# pomodoro_timer.net
KiCad netlist of a schematic drawn in EAGLE
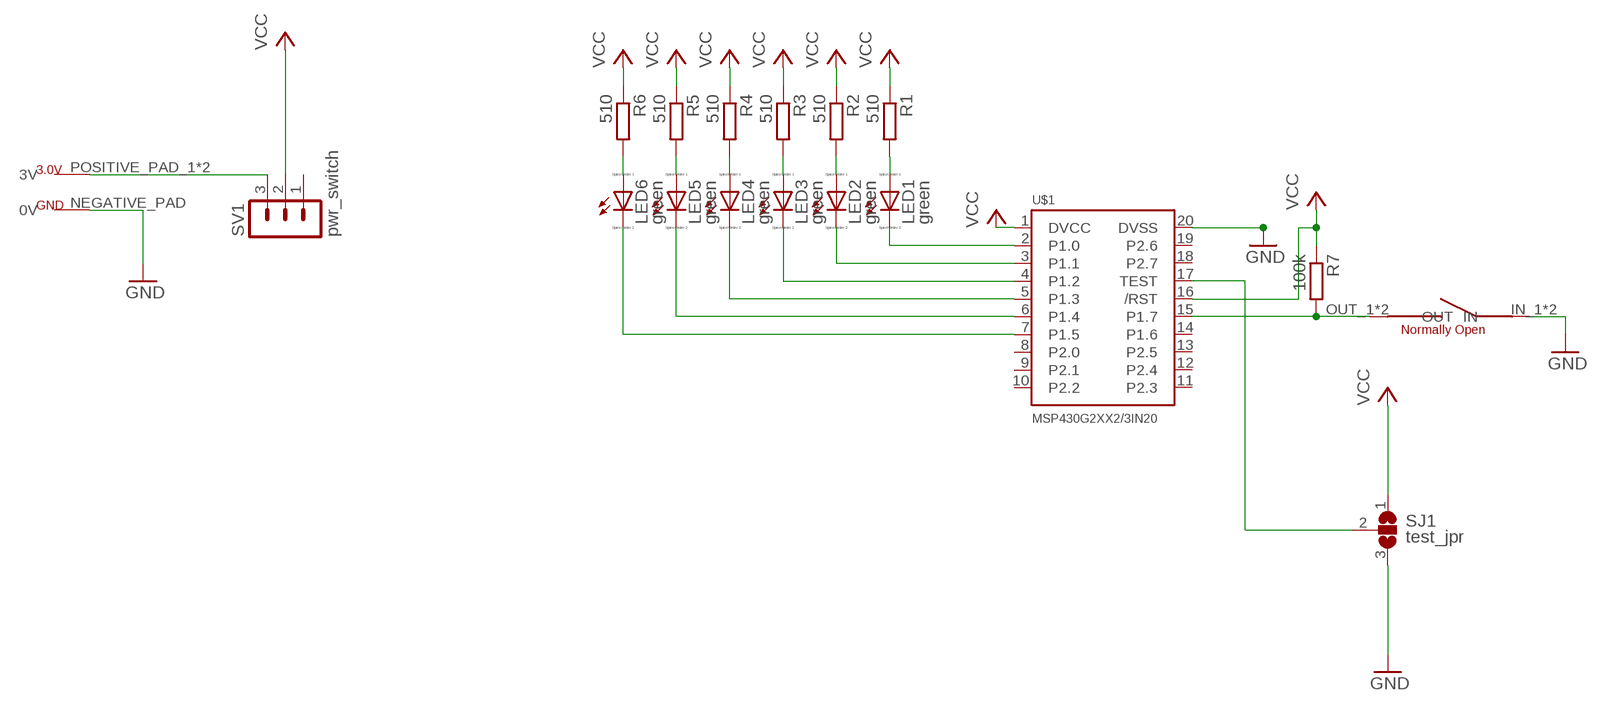
[diagram p0: schematic, sheet 1]

(export (version "E")
  (design (tool "Eeschema 10.0.6"))
  (components
    (comp (ref "LED1")
      (value "green")
      (footprint "eagle-import:LED_1206")
      (libsource (lib "eagle-import") (part "LED_E"))
    )
    (comp (ref "LED2")
      (value "green")
      (footprint "eagle-import:LED_1206")
      (libsource (lib "eagle-import") (part "LED_E"))
    )
    (comp (ref "LED3")
      (value "green")
      (footprint "eagle-import:LED_1206")
      (libsource (lib "eagle-import") (part "LED_E"))
    )
    (comp (ref "LED4")
      (value "green")
      (footprint "eagle-import:LED_1206")
      (libsource (lib "eagle-import") (part "LED_E"))
    )
    (comp (ref "LED5")
      (value "green")
      (footprint "eagle-import:LED_1206")
      (libsource (lib "eagle-import") (part "LED_E"))
    )
    (comp (ref "LED6")
      (value "green")
      (footprint "eagle-import:LED_1206")
      (libsource (lib "eagle-import") (part "LED_E"))
    )
    (comp (ref "R1")
      (value "510")
      (footprint "eagle-import:M1206")
      (libsource (lib "eagle-import") (part "R-EU_M1206"))
    )
    (comp (ref "R2")
      (value "510")
      (footprint "eagle-import:M1206")
      (libsource (lib "eagle-import") (part "R-EU_M1206"))
    )
    (comp (ref "R3")
      (value "510")
      (footprint "eagle-import:M1206")
      (libsource (lib "eagle-import") (part "R-EU_M1206"))
    )
    (comp (ref "R4")
      (value "510")
      (footprint "eagle-import:M1206")
      (libsource (lib "eagle-import") (part "R-EU_M1206"))
    )
    (comp (ref "R5")
      (value "510")
      (footprint "eagle-import:M1206")
      (libsource (lib "eagle-import") (part "R-EU_M1206"))
    )
    (comp (ref "R6")
      (value "510")
      (footprint "eagle-import:M1206")
      (libsource (lib "eagle-import") (part "R-EU_M1206"))
    )
    (comp (ref "R7")
      (value "100k")
      (footprint "eagle-import:M1206")
      (libsource (lib "eagle-import") (part "R-EU_M1206"))
    )
    (comp (ref "SJ1")
      (value "test_jpr")
      (footprint "eagle-import:SJ_2")
      (libsource (lib "eagle-import") (part "SJ2W"))
    )
    (comp (ref "SV1")
      (value "pwr_switch")
      (footprint "eagle-import:MA03-1")
      (libsource (lib "eagle-import") (part "MA03-1"))
    )
    (comp (ref "U$1")
      (value "MSP430G2XX2/3IN20")
      (footprint "eagle-import:DIL20")
      (libsource (lib "eagle-import") (part "MSP430G2XX2/3IN20"))
    )
    (comp (ref "U$2")
      (value "CR2032_HOLDERNORMAL")
      (footprint "eagle-import:CR2032_HOLDER")
      (libsource (lib "eagle-import") (part "CR2032_HOLDERNORMAL"))
    )
    (comp (ref "U$3")
      (value "SWITCH_SIMPLENORMAL")
      (footprint "eagle-import:SWITCH_SIMPLE")
      (libsource (lib "eagle-import") (part "SWITCH_SIMPLENORMAL"))
    )
  )
  (nets
    (net (code "1") (name "GND") (class "Default")
      (node (ref "SJ1") (pin "3") (pinfunction "3_3") (pintype "passive"))
      (node (ref "U$1") (pin "20") (pinfunction "DVSS_20") (pintype "power_in"))
      (node (ref "U$2") (pin "NEGATIVE_PAD") (pinfunction "0V_NEGATIVE_PAD") (pintype "bidirectional"))
      (node (ref "U$3") (pin "IN_1") (pinfunction "IN_IN_1") (pintype "bidirectional"))
      (node (ref "U$3") (pin "IN_2") (pinfunction "IN_IN_2") (pintype "bidirectional"))
    )
    (net (code "2") (name "Net-(LED1-PadA)") (class "Default")
      (node (ref "LED1") (pin "A") (pinfunction "A_A") (pintype "passive"))
      (node (ref "R1") (pin "2") (pinfunction "2_2") (pintype "passive"))
    )
    (net (code "3") (name "Net-(LED2-PadA)") (class "Default")
      (node (ref "LED2") (pin "A") (pinfunction "A_A") (pintype "passive"))
      (node (ref "R2") (pin "2") (pinfunction "2_2") (pintype "passive"))
    )
    (net (code "4") (name "Net-(LED3-PadA)") (class "Default")
      (node (ref "LED3") (pin "A") (pinfunction "A_A") (pintype "passive"))
      (node (ref "R3") (pin "2") (pinfunction "2_2") (pintype "passive"))
    )
    (net (code "5") (name "Net-(LED4-PadA)") (class "Default")
      (node (ref "LED4") (pin "A") (pinfunction "A_A") (pintype "passive"))
      (node (ref "R4") (pin "2") (pinfunction "2_2") (pintype "passive"))
    )
    (net (code "6") (name "Net-(LED5-PadA)") (class "Default")
      (node (ref "LED5") (pin "A") (pinfunction "A_A") (pintype "passive"))
      (node (ref "R5") (pin "2") (pinfunction "2_2") (pintype "passive"))
    )
    (net (code "7") (name "Net-(LED6-PadA)") (class "Default")
      (node (ref "LED6") (pin "A") (pinfunction "A_A") (pintype "passive"))
      (node (ref "R6") (pin "2") (pinfunction "2_2") (pintype "passive"))
    )
    (net (code "8") (name "Net-(SV1-Pad3)") (class "Default")
      (node (ref "SV1") (pin "3") (pinfunction "3_3") (pintype "passive"))
      (node (ref "U$2") (pin "POSITIVE_PAD_1") (pinfunction "3V_POSITIVE_PAD_1") (pintype "bidirectional"))
      (node (ref "U$2") (pin "POSITIVE_PAD_2") (pinfunction "3V_POSITIVE_PAD_2") (pintype "bidirectional"))
    )
    (net (code "9") (name "Net-(U$1-P1.0)") (class "Default")
      (node (ref "LED1") (pin "C") (pinfunction "C_C") (pintype "passive"))
      (node (ref "U$1") (pin "2") (pinfunction "P1.0_2") (pintype "bidirectional"))
    )
    (net (code "10") (name "Net-(U$1-P1.1)") (class "Default")
      (node (ref "LED2") (pin "C") (pinfunction "C_C") (pintype "passive"))
      (node (ref "U$1") (pin "3") (pinfunction "P1.1_3") (pintype "bidirectional"))
    )
    (net (code "11") (name "Net-(U$1-P1.2)") (class "Default")
      (node (ref "LED3") (pin "C") (pinfunction "C_C") (pintype "passive"))
      (node (ref "U$1") (pin "4") (pinfunction "P1.2_4") (pintype "bidirectional"))
    )
    (net (code "12") (name "Net-(U$1-P1.3)") (class "Default")
      (node (ref "LED4") (pin "C") (pinfunction "C_C") (pintype "passive"))
      (node (ref "U$1") (pin "5") (pinfunction "P1.3_5") (pintype "bidirectional"))
    )
    (net (code "13") (name "Net-(U$1-P1.4)") (class "Default")
      (node (ref "LED5") (pin "C") (pinfunction "C_C") (pintype "passive"))
      (node (ref "U$1") (pin "6") (pinfunction "P1.4_6") (pintype "bidirectional"))
    )
    (net (code "14") (name "Net-(U$1-P1.5)") (class "Default")
      (node (ref "LED6") (pin "C") (pinfunction "C_C") (pintype "passive"))
      (node (ref "U$1") (pin "7") (pinfunction "P1.5_7") (pintype "bidirectional"))
    )
    (net (code "15") (name "Net-(U$1-P1.7)") (class "Default")
      (node (ref "R7") (pin "2") (pinfunction "2_2") (pintype "passive"))
      (node (ref "U$1") (pin "15") (pinfunction "P1.7_15") (pintype "bidirectional"))
      (node (ref "U$3") (pin "OUT_1") (pinfunction "OUT_OUT_1") (pintype "bidirectional"))
      (node (ref "U$3") (pin "OUT_2") (pinfunction "OUT_OUT_2") (pintype "bidirectional"))
    )
    (net (code "16") (name "Net-(U$1-TEST)") (class "Default")
      (node (ref "SJ1") (pin "2") (pinfunction "2_2") (pintype "passive"))
      (node (ref "U$1") (pin "17") (pinfunction "TEST_17") (pintype "bidirectional"))
    )
    (net (code "17") (name "VCC") (class "Default")
      (node (ref "R1") (pin "1") (pinfunction "1_1") (pintype "passive"))
      (node (ref "R2") (pin "1") (pinfunction "1_1") (pintype "passive"))
      (node (ref "R3") (pin "1") (pinfunction "1_1") (pintype "passive"))
      (node (ref "R4") (pin "1") (pinfunction "1_1") (pintype "passive"))
      (node (ref "R5") (pin "1") (pinfunction "1_1") (pintype "passive"))
      (node (ref "R6") (pin "1") (pinfunction "1_1") (pintype "passive"))
      (node (ref "R7") (pin "1") (pinfunction "1_1") (pintype "passive"))
      (node (ref "SJ1") (pin "1") (pinfunction "1_1") (pintype "passive"))
      (node (ref "SV1") (pin "2") (pinfunction "2_2") (pintype "passive"))
      (node (ref "U$1") (pin "1") (pinfunction "DVCC_1") (pintype "power_in"))
      (node (ref "U$1") (pin "16") (pinfunction "/RST_16") (pintype "bidirectional"))
    )
    (net (code "18") (name "unconnected-(SV1-Pad1)") (class "Default")
      (node (ref "SV1") (pin "1") (pinfunction "1_1") (pintype "passive"))
    )
    (net (code "19") (name "unconnected-(U$1-P1.6-Pad14)") (class "Default")
      (node (ref "U$1") (pin "14") (pinfunction "P1.6_14") (pintype "bidirectional"))
    )
    (net (code "20") (name "unconnected-(U$1-P2.0-Pad8)") (class "Default")
      (node (ref "U$1") (pin "8") (pinfunction "P2.0_8") (pintype "bidirectional"))
    )
    (net (code "21") (name "unconnected-(U$1-P2.1-Pad9)") (class "Default")
      (node (ref "U$1") (pin "9") (pinfunction "P2.1_9") (pintype "bidirectional"))
    )
    (net (code "22") (name "unconnected-(U$1-P2.2-Pad10)") (class "Default")
      (node (ref "U$1") (pin "10") (pinfunction "P2.2_10") (pintype "bidirectional"))
    )
    (net (code "23") (name "unconnected-(U$1-P2.3-Pad11)") (class "Default")
      (node (ref "U$1") (pin "11") (pinfunction "P2.3_11") (pintype "bidirectional"))
    )
    (net (code "24") (name "unconnected-(U$1-P2.4-Pad12)") (class "Default")
      (node (ref "U$1") (pin "12") (pinfunction "P2.4_12") (pintype "bidirectional"))
    )
    (net (code "25") (name "unconnected-(U$1-P2.5-Pad13)") (class "Default")
      (node (ref "U$1") (pin "13") (pinfunction "P2.5_13") (pintype "bidirectional"))
    )
    (net (code "26") (name "unconnected-(U$1-P2.6-Pad19)") (class "Default")
      (node (ref "U$1") (pin "19") (pinfunction "P2.6_19") (pintype "bidirectional"))
    )
    (net (code "27") (name "unconnected-(U$1-P2.7-Pad18)") (class "Default")
      (node (ref "U$1") (pin "18") (pinfunction "P2.7_18") (pintype "bidirectional"))
    )
  )
)
